# Microcontroller_and_Memory.net
KiCad netlist of a schematic drawn in Altium Designer
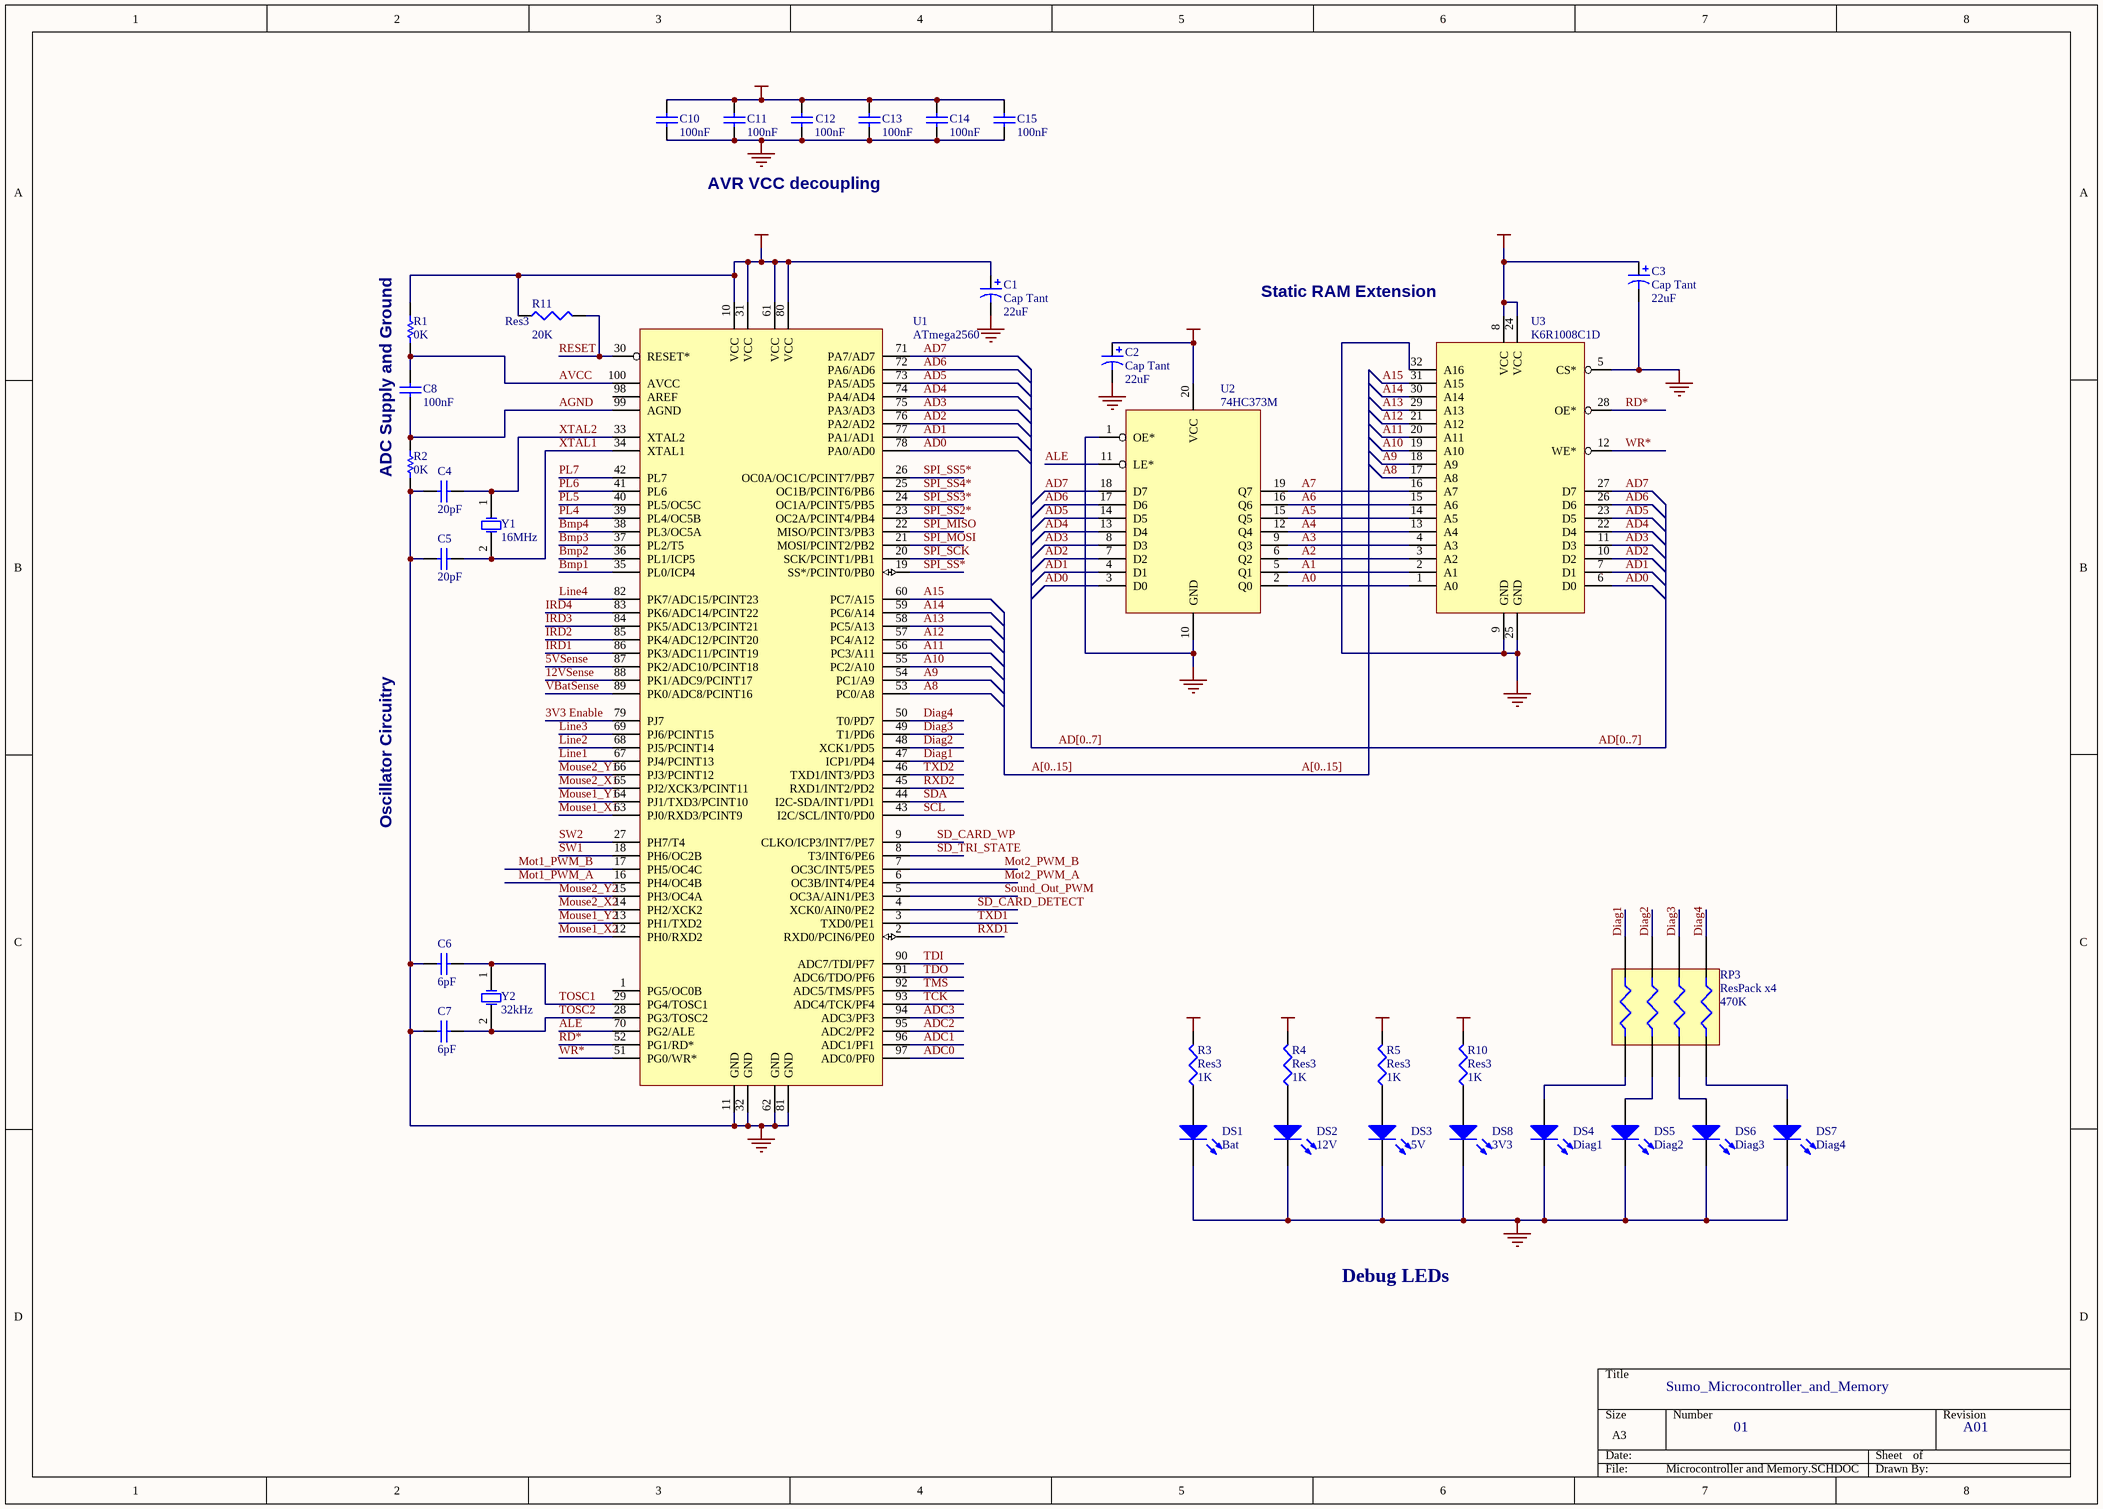
[diagram p0: Microcontroller and Memory.SCHDOC]

(export (version "E")
  (design (tool "Eeschema 10.0.6"))
  (components
    (comp (ref "C1")
      (value "Cap Tant")
      (footprint "CAPR5-4X5")
      (description "Polarized Capacitor (Axial)")
      (fields (field (name "ALTIUM_VALUE") "22uF") (field (name "PUBLISHER") "Altium Limited"))
      (libsource (lib "Miscellaneous Devices") (part "Cap Pol2"))
    )
    (comp (ref "C2")
      (value "Cap Tant")
      (footprint "CAPR5-4X5")
      (description "Polarized Capacitor (Axial)")
      (fields (field (name "ALTIUM_VALUE") "22uF") (field (name "PUBLISHER") "Altium Limited"))
      (libsource (lib "Miscellaneous Devices") (part "Cap Pol2"))
    )
    (comp (ref "C3")
      (value "Cap Tant")
      (footprint "CAPR5-4X5")
      (description "Polarized Capacitor (Axial)")
      (fields (field (name "ALTIUM_VALUE") "22uF") (field (name "PUBLISHER") "Altium Limited"))
      (libsource (lib "Miscellaneous Devices") (part "Cap Pol2"))
    )
    (comp (ref "C4")
      (value "20pF")
      (footprint "CC2012-0805")
      (description "Capacitor")
      (fields (field (name "PUBLISHER") "Altium Limited"))
      (libsource (lib "Miscellaneous Devices") (part "Cap"))
    )
    (comp (ref "C5")
      (value "20pF")
      (footprint "CC2012-0805")
      (description "Capacitor")
      (fields (field (name "PUBLISHER") "Altium Limited"))
      (libsource (lib "Miscellaneous Devices") (part "Cap"))
    )
    (comp (ref "C6")
      (value "6pF")
      (footprint "CC2012-0805")
      (description "Capacitor")
      (fields (field (name "PUBLISHER") "Altium Limited"))
      (libsource (lib "Miscellaneous Devices") (part "Cap"))
    )
    (comp (ref "C7")
      (value "6pF")
      (footprint "CC2012-0805")
      (description "Capacitor")
      (fields (field (name "PUBLISHER") "Altium Limited"))
      (libsource (lib "Miscellaneous Devices") (part "Cap"))
    )
    (comp (ref "C8")
      (value "100nF")
      (footprint "CC2012-0805")
      (description "Capacitor")
      (fields (field (name "PUBLISHER") "Altium Limited"))
      (libsource (lib "Miscellaneous Devices") (part "Cap"))
    )
    (comp (ref "C10")
      (value "100nF")
      (footprint "CC2012-0805")
      (description "Capacitor (Semiconductor SIM Model)")
      (fields (field (name "Comment") "Cap Semi") (field (name "PUBLISHER") "Altium Limited"))
      (libsource (lib "Miscellaneous Devices") (part "Cap Semi"))
    )
    (comp (ref "C11")
      (value "100nF")
      (footprint "CC2012-0805")
      (description "Capacitor (Semiconductor SIM Model)")
      (fields (field (name "Comment") "Cap Semi") (field (name "PUBLISHER") "Altium Limited"))
      (libsource (lib "Miscellaneous Devices") (part "Cap Semi"))
    )
    (comp (ref "C12")
      (value "100nF")
      (footprint "CC2012-0805")
      (description "Capacitor (Semiconductor SIM Model)")
      (fields (field (name "Comment") "Cap Semi") (field (name "PUBLISHER") "Altium Limited"))
      (libsource (lib "Miscellaneous Devices") (part "Cap Semi"))
    )
    (comp (ref "C13")
      (value "100nF")
      (footprint "CC2012-0805")
      (description "Capacitor (Semiconductor SIM Model)")
      (fields (field (name "Comment") "Cap Semi") (field (name "PUBLISHER") "Altium Limited"))
      (libsource (lib "Miscellaneous Devices") (part "Cap Semi"))
    )
    (comp (ref "C14")
      (value "100nF")
      (footprint "CC2012-0805")
      (description "Capacitor (Semiconductor SIM Model)")
      (fields (field (name "Comment") "Cap Semi") (field (name "PUBLISHER") "Altium Limited"))
      (libsource (lib "Miscellaneous Devices") (part "Cap Semi"))
    )
    (comp (ref "C15")
      (value "100nF")
      (footprint "CC2012-0805")
      (description "Capacitor (Semiconductor SIM Model)")
      (fields (field (name "Comment") "Cap Semi") (field (name "PUBLISHER") "Altium Limited"))
      (libsource (lib "Miscellaneous Devices") (part "Cap Semi"))
    )
    (comp (ref "DS1")
      (value "Bat")
      (footprint "SMD _LED")
      (description "Typical BLUE SiC LED")
      (fields (field (name "PUBLISHER") "Altium Limited"))
      (libsource (lib "Miscellaneous Devices") (part "LED3"))
    )
    (comp (ref "DS2")
      (value "12V")
      (footprint "SMD _LED")
      (description "Typical BLUE SiC LED")
      (fields (field (name "PUBLISHER") "Altium Limited"))
      (libsource (lib "Miscellaneous Devices") (part "LED3"))
    )
    (comp (ref "DS3")
      (value "5V")
      (footprint "SMD _LED")
      (description "Typical BLUE SiC LED")
      (fields (field (name "PUBLISHER") "Altium Limited"))
      (libsource (lib "Miscellaneous Devices") (part "LED3"))
    )
    (comp (ref "DS4")
      (value "Diag1")
      (footprint "SMD _LED")
      (description "Typical BLUE SiC LED")
      (fields (field (name "PUBLISHER") "Altium Limited"))
      (libsource (lib "Miscellaneous Devices") (part "LED3"))
    )
    (comp (ref "DS5")
      (value "Diag2")
      (footprint "SMD _LED")
      (description "Typical BLUE SiC LED")
      (fields (field (name "PUBLISHER") "Altium Limited"))
      (libsource (lib "Miscellaneous Devices") (part "LED3"))
    )
    (comp (ref "DS6")
      (value "Diag3")
      (footprint "SMD _LED")
      (description "Typical BLUE SiC LED")
      (fields (field (name "PUBLISHER") "Altium Limited"))
      (libsource (lib "Miscellaneous Devices") (part "LED3"))
    )
    (comp (ref "DS7")
      (value "Diag4")
      (footprint "SMD _LED")
      (description "Typical BLUE SiC LED")
      (fields (field (name "PUBLISHER") "Altium Limited"))
      (libsource (lib "Miscellaneous Devices") (part "LED3"))
    )
    (comp (ref "DS8")
      (value "3V3")
      (footprint "SMD _LED")
      (description "Typical BLUE SiC LED")
      (fields (field (name "PUBLISHER") "Altium Limited"))
      (libsource (lib "Miscellaneous Devices") (part "LED3"))
    )
    (comp (ref "R1")
      (value "0K")
      (footprint "AXIAL-0.3")
      (description "Resistor")
      (fields (field (name "PUBLISHER") "Altium Limited"))
      (libsource (lib "Miscellaneous Devices") (part "Res1"))
    )
    (comp (ref "R2")
      (value "0K")
      (footprint "AXIAL-0.3")
      (description "Resistor")
      (fields (field (name "PUBLISHER") "Altium Limited"))
      (libsource (lib "Miscellaneous Devices") (part "Res1"))
    )
    (comp (ref "R3")
      (value "Res3")
      (footprint "R2012-0805")
      (description "Resistor")
      (fields (field (name "ALTIUM_VALUE") "1K") (field (name "PUBLISHER") "Altium Limited"))
      (libsource (lib "Miscellaneous Devices") (part "Res3"))
    )
    (comp (ref "R4")
      (value "Res3")
      (footprint "R2012-0805")
      (description "Resistor")
      (fields (field (name "ALTIUM_VALUE") "1K") (field (name "PUBLISHER") "Altium Limited"))
      (libsource (lib "Miscellaneous Devices") (part "Res3"))
    )
    (comp (ref "R5")
      (value "Res3")
      (footprint "R2012-0805")
      (description "Resistor")
      (fields (field (name "ALTIUM_VALUE") "1K") (field (name "PUBLISHER") "Altium Limited"))
      (libsource (lib "Miscellaneous Devices") (part "Res3"))
    )
    (comp (ref "R10")
      (value "Res3")
      (footprint "R2012-0805")
      (description "Resistor")
      (fields (field (name "ALTIUM_VALUE") "1K") (field (name "PUBLISHER") "Altium Limited"))
      (libsource (lib "Miscellaneous Devices") (part "Res3"))
    )
    (comp (ref "R11")
      (value "Res3")
      (footprint "R2012-0805")
      (description "Resistor")
      (fields (field (name "ALTIUM_VALUE") "20K") (field (name "PUBLISHER") "Altium Limited"))
      (libsource (lib "Miscellaneous Devices") (part "Res3"))
    )
    (comp (ref "RP3")
      (value "ResPack x4")
      (footprint "4x0603 Resistor pack")
      (fields (field (name "ALTIUM_VALUE") "470K"))
      (libsource (lib "Sumo") (part "ResPack x4"))
    )
    (comp (ref "U1")
      (value "ATmega2560")
      (footprint "F-QFP14X14-G100/Z17N")
      (description "Atmel ATmega2560 MCU")
      (libsource (lib "Sumo") (part "ATmega2560"))
    )
    (comp (ref "U2")
      (value "74HC373M")
      (footprint "SO-G20/Y1.45")
      (description "Octal 8-bit D-type Latch")
      (libsource (lib "Schematic Library") (part "74373"))
    )
    (comp (ref "U3")
      (value "K6R1008C1D")
      (footprint "SO-G32/Y1.45")
      (description "Samsung 128Kx8 High-Speed Static RAM")
      (libsource (lib "Schematic Library") (part "K6R1008C1D"))
    )
    (comp (ref "Y1")
      (value "16MHz")
      (footprint "Crystal HC49SLF")
      (description "Crystal Oscillator")
      (fields (field (name "PUBLISHER") "Altium Limited"))
      (libsource (lib "Miscellaneous Devices") (part "XTAL"))
    )
    (comp (ref "Y2")
      (value "32kHz")
      (footprint "Crystal CFS206")
      (description "Crystal Oscillator")
      (fields (field (name "PUBLISHER") "Altium Limited"))
      (libsource (lib "Miscellaneous Devices") (part "XTAL"))
    )
  )
  (nets
    (net (code "1") (name "/3V3 Enable") (class "Default")
      (node (ref "U1") (pin "79") (pinfunction "PJ7_79") (pintype "passive"))
    )
    (net (code "2") (name "/5VSense") (class "Default")
      (node (ref "U1") (pin "87") (pinfunction "PK2/ADC10/PCINT18_87") (pintype "passive"))
    )
    (net (code "3") (name "/12VSense") (class "Default")
      (node (ref "U1") (pin "88") (pinfunction "PK1/ADC9/PCINT17_88") (pintype "passive"))
    )
    (net (code "4") (name "/A0") (class "Default")
      (node (ref "U2") (pin "2") (pinfunction "Q0_2") (pintype "passive"))
      (node (ref "U3") (pin "1") (pinfunction "A0_1") (pintype "passive"))
    )
    (net (code "5") (name "/A1") (class "Default")
      (node (ref "U2") (pin "5") (pinfunction "Q1_5") (pintype "passive"))
      (node (ref "U3") (pin "2") (pinfunction "A1_2") (pintype "passive"))
    )
    (net (code "6") (name "/A2") (class "Default")
      (node (ref "U2") (pin "6") (pinfunction "Q2_6") (pintype "passive"))
      (node (ref "U3") (pin "3") (pinfunction "A2_3") (pintype "passive"))
    )
    (net (code "7") (name "/A3") (class "Default")
      (node (ref "U2") (pin "9") (pinfunction "Q3_9") (pintype "passive"))
      (node (ref "U3") (pin "4") (pinfunction "A3_4") (pintype "passive"))
    )
    (net (code "8") (name "/A4") (class "Default")
      (node (ref "U2") (pin "12") (pinfunction "Q4_12") (pintype "passive"))
      (node (ref "U3") (pin "13") (pinfunction "A4_13") (pintype "passive"))
    )
    (net (code "9") (name "/A5") (class "Default")
      (node (ref "U2") (pin "15") (pinfunction "Q5_15") (pintype "passive"))
      (node (ref "U3") (pin "14") (pinfunction "A5_14") (pintype "passive"))
    )
    (net (code "10") (name "/A6") (class "Default")
      (node (ref "U2") (pin "16") (pinfunction "Q6_16") (pintype "passive"))
      (node (ref "U3") (pin "15") (pinfunction "A6_15") (pintype "passive"))
    )
    (net (code "11") (name "/A7") (class "Default")
      (node (ref "U2") (pin "19") (pinfunction "Q7_19") (pintype "passive"))
      (node (ref "U3") (pin "16") (pinfunction "A7_16") (pintype "passive"))
    )
    (net (code "12") (name "/A8") (class "Default")
      (node (ref "U1") (pin "53") (pinfunction "PC0/A8_53") (pintype "passive"))
      (node (ref "U3") (pin "17") (pinfunction "A8_17") (pintype "passive"))
    )
    (net (code "13") (name "/A9") (class "Default")
      (node (ref "U1") (pin "54") (pinfunction "PC1/A9_54") (pintype "passive"))
      (node (ref "U3") (pin "18") (pinfunction "A9_18") (pintype "passive"))
    )
    (net (code "14") (name "/A10") (class "Default")
      (node (ref "U1") (pin "55") (pinfunction "PC2/A10_55") (pintype "passive"))
      (node (ref "U3") (pin "19") (pinfunction "A10_19") (pintype "passive"))
    )
    (net (code "15") (name "/A11") (class "Default")
      (node (ref "U1") (pin "56") (pinfunction "PC3/A11_56") (pintype "passive"))
      (node (ref "U3") (pin "20") (pinfunction "A11_20") (pintype "passive"))
    )
    (net (code "16") (name "/A12") (class "Default")
      (node (ref "U1") (pin "57") (pinfunction "PC4/A12_57") (pintype "passive"))
      (node (ref "U3") (pin "21") (pinfunction "A12_21") (pintype "passive"))
    )
    (net (code "17") (name "/A13") (class "Default")
      (node (ref "U1") (pin "58") (pinfunction "PC5/A13_58") (pintype "passive"))
      (node (ref "U3") (pin "29") (pinfunction "A13_29") (pintype "passive"))
    )
    (net (code "18") (name "/A14") (class "Default")
      (node (ref "U1") (pin "59") (pinfunction "PC6/A14_59") (pintype "passive"))
      (node (ref "U3") (pin "30") (pinfunction "A14_30") (pintype "passive"))
    )
    (net (code "19") (name "/A15") (class "Default")
      (node (ref "U1") (pin "60") (pinfunction "PC7/A15_60") (pintype "passive"))
      (node (ref "U3") (pin "31") (pinfunction "A15_31") (pintype "passive"))
    )
    (net (code "20") (name "/AD0") (class "Default")
      (node (ref "U1") (pin "78") (pinfunction "PA0/AD0_78") (pintype "passive"))
      (node (ref "U2") (pin "3") (pinfunction "D0_3") (pintype "passive"))
      (node (ref "U3") (pin "6") (pinfunction "D0_6") (pintype "passive"))
    )
    (net (code "21") (name "/AD1") (class "Default")
      (node (ref "U1") (pin "77") (pinfunction "PA1/AD1_77") (pintype "passive"))
      (node (ref "U2") (pin "4") (pinfunction "D1_4") (pintype "passive"))
      (node (ref "U3") (pin "7") (pinfunction "D1_7") (pintype "passive"))
    )
    (net (code "22") (name "/AD2") (class "Default")
      (node (ref "U1") (pin "76") (pinfunction "PA2/AD2_76") (pintype "passive"))
      (node (ref "U2") (pin "7") (pinfunction "D2_7") (pintype "passive"))
      (node (ref "U3") (pin "10") (pinfunction "D2_10") (pintype "passive"))
    )
    (net (code "23") (name "/AD3") (class "Default")
      (node (ref "U1") (pin "75") (pinfunction "PA3/AD3_75") (pintype "passive"))
      (node (ref "U2") (pin "8") (pinfunction "D3_8") (pintype "passive"))
      (node (ref "U3") (pin "11") (pinfunction "D3_11") (pintype "passive"))
    )
    (net (code "24") (name "/AD4") (class "Default")
      (node (ref "U1") (pin "74") (pinfunction "PA4/AD4_74") (pintype "passive"))
      (node (ref "U2") (pin "13") (pinfunction "D4_13") (pintype "passive"))
      (node (ref "U3") (pin "22") (pinfunction "D4_22") (pintype "passive"))
    )
    (net (code "25") (name "/AD5") (class "Default")
      (node (ref "U1") (pin "73") (pinfunction "PA5/AD5_73") (pintype "passive"))
      (node (ref "U2") (pin "14") (pinfunction "D5_14") (pintype "passive"))
      (node (ref "U3") (pin "23") (pinfunction "D5_23") (pintype "passive"))
    )
    (net (code "26") (name "/AD6") (class "Default")
      (node (ref "U1") (pin "72") (pinfunction "PA6/AD6_72") (pintype "passive"))
      (node (ref "U2") (pin "17") (pinfunction "D6_17") (pintype "passive"))
      (node (ref "U3") (pin "26") (pinfunction "D6_26") (pintype "passive"))
    )
    (net (code "27") (name "/AD7") (class "Default")
      (node (ref "U1") (pin "71") (pinfunction "PA7/AD7_71") (pintype "passive"))
      (node (ref "U2") (pin "18") (pinfunction "D7_18") (pintype "passive"))
      (node (ref "U3") (pin "27") (pinfunction "D7_27") (pintype "passive"))
    )
    (net (code "28") (name "/ADC0") (class "Default")
      (node (ref "U1") (pin "97") (pinfunction "ADC0/PF0_97") (pintype "passive"))
    )
    (net (code "29") (name "/ADC1") (class "Default")
      (node (ref "U1") (pin "96") (pinfunction "ADC1/PF1_96") (pintype "passive"))
    )
    (net (code "30") (name "/ADC2") (class "Default")
      (node (ref "U1") (pin "95") (pinfunction "ADC2/PF2_95") (pintype "passive"))
    )
    (net (code "31") (name "/ADC3") (class "Default")
      (node (ref "U1") (pin "94") (pinfunction "ADC3/PF3_94") (pintype "passive"))
    )
    (net (code "33") (name "/AGND") (class "Default")
      (node (ref "C8") (pin "2") (pinfunction "2_2") (pintype "passive"))
      (node (ref "R2") (pin "2") (pinfunction "2_2") (pintype "passive"))
      (node (ref "U1") (pin "99") (pinfunction "AGND_99") (pintype "passive"))
    )
    (net (code "34") (name "/ALE") (class "Default")
      (node (ref "U1") (pin "70") (pinfunction "PG2/ALE_70") (pintype "passive"))
      (node (ref "U2") (pin "11") (pinfunction "LE*_11") (pintype "passive"))
    )
    (net (code "35") (name "/AVCC") (class "Default")
      (node (ref "C8") (pin "1") (pinfunction "1_1") (pintype "passive"))
      (node (ref "R1") (pin "1") (pinfunction "1_1") (pintype "passive"))
      (node (ref "U1") (pin "100") (pinfunction "AVCC_100") (pintype "passive"))
    )
    (net (code "37") (name "/Bmp1") (class "Default")
      (node (ref "U1") (pin "35") (pinfunction "PL0/ICP4_35") (pintype "passive"))
    )
    (net (code "38") (name "/Bmp2") (class "Default")
      (node (ref "U1") (pin "36") (pinfunction "PL1/ICP5_36") (pintype "passive"))
    )
    (net (code "39") (name "/Bmp3") (class "Default")
      (node (ref "U1") (pin "37") (pinfunction "PL2/T5_37") (pintype "passive"))
    )
    (net (code "40") (name "/Bmp4") (class "Default")
      (node (ref "U1") (pin "38") (pinfunction "PL3/OC5A_38") (pintype "passive"))
    )
    (net (code "41") (name "/Diag1") (class "Default")
      (node (ref "RP3") (pin "8") (pintype "passive"))
      (node (ref "U1") (pin "47") (pinfunction "ICP1/PD4_47") (pintype "passive"))
    )
    (net (code "42") (name "/Diag2") (class "Default")
      (node (ref "RP3") (pin "7") (pintype "passive"))
      (node (ref "U1") (pin "48") (pinfunction "XCK1/PD5_48") (pintype "passive"))
    )
    (net (code "43") (name "/Diag3") (class "Default")
      (node (ref "RP3") (pin "6") (pintype "passive"))
      (node (ref "U1") (pin "49") (pinfunction "T1/PD6_49") (pintype "passive"))
    )
    (net (code "44") (name "/Diag4") (class "Default")
      (node (ref "RP3") (pin "5") (pintype "passive"))
      (node (ref "U1") (pin "50") (pinfunction "T0/PD7_50") (pintype "passive"))
    )
    (net (code "45") (name "/IRD1") (class "Default")
      (node (ref "U1") (pin "86") (pinfunction "PK3/ADC11/PCINT19_86") (pintype "passive"))
    )
    (net (code "46") (name "/IRD2") (class "Default")
      (node (ref "U1") (pin "85") (pinfunction "PK4/ADC12/PCINT20_85") (pintype "passive"))
    )
    (net (code "47") (name "/IRD3") (class "Default")
      (node (ref "U1") (pin "84") (pinfunction "PK5/ADC13/PCINT21_84") (pintype "passive"))
    )
    (net (code "48") (name "/IRD4") (class "Default")
      (node (ref "U1") (pin "83") (pinfunction "PK6/ADC14/PCINT22_83") (pintype "passive"))
    )
    (net (code "49") (name "/Line1") (class "Default")
      (node (ref "U1") (pin "67") (pinfunction "PJ4/PCINT13_67") (pintype "passive"))
    )
    (net (code "50") (name "/Line2") (class "Default")
      (node (ref "U1") (pin "68") (pinfunction "PJ5/PCINT14_68") (pintype "passive"))
    )
    (net (code "51") (name "/Line3") (class "Default")
      (node (ref "U1") (pin "69") (pinfunction "PJ6/PCINT15_69") (pintype "passive"))
    )
    (net (code "52") (name "/Line4") (class "Default")
      (node (ref "U1") (pin "82") (pinfunction "PK7/ADC15/PCINT23_82") (pintype "passive"))
    )
    (net (code "53") (name "/Mot1_PWM_A") (class "Default")
      (node (ref "U1") (pin "16") (pinfunction "PH4/OC4B_16") (pintype "passive"))
    )
    (net (code "54") (name "/Mot1_PWM_B") (class "Default")
      (node (ref "U1") (pin "17") (pinfunction "PH5/OC4C_17") (pintype "passive"))
    )
    (net (code "55") (name "/Mot2_PWM_A") (class "Default")
      (node (ref "U1") (pin "6") (pinfunction "OC3B/INT4/PE4_6") (pintype "passive"))
    )
    (net (code "56") (name "/Mot2_PWM_B") (class "Default")
      (node (ref "U1") (pin "7") (pinfunction "OC3C/INT5/PE5_7") (pintype "passive"))
    )
    (net (code "57") (name "/Mouse1_X1") (class "Default")
      (node (ref "U1") (pin "63") (pinfunction "PJ0/RXD3/PCINT9_63") (pintype "passive"))
    )
    (net (code "58") (name "/Mouse1_X2") (class "Default")
      (node (ref "U1") (pin "12") (pinfunction "PH0/RXD2_12") (pintype "passive"))
    )
    (net (code "59") (name "/Mouse1_Y1") (class "Default")
      (node (ref "U1") (pin "64") (pinfunction "PJ1/TXD3/PCINT10_64") (pintype "passive"))
    )
    (net (code "60") (name "/Mouse1_Y2") (class "Default")
      (node (ref "U1") (pin "13") (pinfunction "PH1/TXD2_13") (pintype "passive"))
    )
    (net (code "61") (name "/Mouse2_X1") (class "Default")
      (node (ref "U1") (pin "65") (pinfunction "PJ2/XCK3/PCINT11_65") (pintype "passive"))
    )
    (net (code "62") (name "/Mouse2_X2") (class "Default")
      (node (ref "U1") (pin "14") (pinfunction "PH2/XCK2_14") (pintype "passive"))
    )
    (net (code "63") (name "/Mouse2_Y1") (class "Default")
      (node (ref "U1") (pin "66") (pinfunction "PJ3/PCINT12_66") (pintype "passive"))
    )
    (net (code "64") (name "/Mouse2_Y2") (class "Default")
      (node (ref "U1") (pin "15") (pinfunction "PH3/OC4A_15") (pintype "passive"))
    )
    (net (code "65") (name "/PL4") (class "Default")
      (node (ref "U1") (pin "39") (pinfunction "PL4/OC5B_39") (pintype "passive"))
    )
    (net (code "66") (name "/PL5") (class "Default")
      (node (ref "U1") (pin "40") (pinfunction "PL5/OC5C_40") (pintype "passive"))
    )
    (net (code "67") (name "/PL6") (class "Default")
      (node (ref "U1") (pin "41") (pinfunction "PL6_41") (pintype "passive"))
    )
    (net (code "68") (name "/PL7") (class "Default")
      (node (ref "U1") (pin "42") (pinfunction "PL7_42") (pintype "passive"))
    )
    (net (code "69") (name "/RD*") (class "Default")
      (node (ref "U1") (pin "52") (pinfunction "PG1/RD*_52") (pintype "passive"))
      (node (ref "U3") (pin "28") (pinfunction "OE*_28") (pintype "passive"))
    )
    (net (code "70") (name "/RESET") (class "Default")
      (node (ref "R11") (pin "2") (pinfunction "2_2") (pintype "passive"))
      (node (ref "U1") (pin "30") (pinfunction "RESET*_30") (pintype "passive"))
    )
    (net (code "71") (name "/RXD1") (class "Default")
      (node (ref "U1") (pin "2") (pinfunction "RXD0/PCIN6/PE0_2") (pintype "bidirectional"))
    )
    (net (code "72") (name "/RXD2") (class "Default")
      (node (ref "U1") (pin "45") (pinfunction "RXD1/INT2/PD2_45") (pintype "passive"))
    )
    (net (code "73") (name "/SCL") (class "Default")
      (node (ref "U1") (pin "43") (pinfunction "I2C/SCL/INT0/PD0_43") (pintype "passive"))
    )
    (net (code "74") (name "/SDA") (class "Default")
      (node (ref "U1") (pin "44") (pinfunction "I2C-SDA/INT1/PD1_44") (pintype "passive"))
    )
    (net (code "75") (name "/SD_CARD_DETECT") (class "Default")
      (node (ref "U1") (pin "4") (pinfunction "XCK0/AIN0/PE2_4") (pintype "passive"))
    )
    (net (code "76") (name "/SD_CARD_WP") (class "Default")
      (node (ref "U1") (pin "9") (pinfunction "CLKO/ICP3/INT7/PE7_9") (pintype "passive"))
    )
    (net (code "77") (name "/SD_TRI_STATE") (class "Default")
      (node (ref "U1") (pin "8") (pinfunction "T3/INT6/PE6_8") (pintype "passive"))
    )
    (net (code "78") (name "/SPI_MISO") (class "Default")
      (node (ref "U1") (pin "22") (pinfunction "MISO/PCINT3/PB3_22") (pintype "passive"))
    )
    (net (code "79") (name "/SPI_MOSI") (class "Default")
      (node (ref "U1") (pin "21") (pinfunction "MOSI/PCINT2/PB2_21") (pintype "passive"))
    )
    (net (code "80") (name "/SPI_SCK") (class "Default")
      (node (ref "U1") (pin "20") (pinfunction "SCK/PCINT1/PB1_20") (pintype "passive"))
    )
    (net (code "81") (name "/SPI_SS*") (class "Default")
      (node (ref "U1") (pin "19") (pinfunction "SS*/PCINT0/PB0_19") (pintype "bidirectional"))
    )
    (net (code "82") (name "/SPI_SS2*") (class "Default")
      (node (ref "U1") (pin "23") (pinfunction "OC2A/PCINT4/PB4_23") (pintype "passive"))
    )
    (net (code "83") (name "/SPI_SS3*") (class "Default")
      (node (ref "U1") (pin "24") (pinfunction "OC1A/PCINT5/PB5_24") (pintype "passive"))
    )
    (net (code "84") (name "/SPI_SS4*") (class "Default")
      (node (ref "U1") (pin "25") (pinfunction "OC1B/PCINT6/PB6_25") (pintype "passive"))
    )
    (net (code "85") (name "/SPI_SS5*") (class "Default")
      (node (ref "U1") (pin "26") (pinfunction "OC0A/OC1C/PCINT7/PB7_26") (pintype "passive"))
    )
    (net (code "86") (name "/SW1") (class "Default")
      (node (ref "U1") (pin "18") (pinfunction "PH6/OC2B_18") (pintype "passive"))
    )
    (net (code "87") (name "/SW2") (class "Default")
      (node (ref "U1") (pin "27") (pinfunction "PH7/T4_27") (pintype "passive"))
    )
    (net (code "88") (name "/Sound_Out_PWM") (class "Default")
      (node (ref "U1") (pin "5") (pinfunction "OC3A/AIN1/PE3_5") (pintype "passive"))
    )
    (net (code "89") (name "/TCK") (class "Default")
      (node (ref "U1") (pin "93") (pinfunction "ADC4/TCK/PF4_93") (pintype "passive"))
    )
    (net (code "90") (name "/TDI") (class "Default")
      (node (ref "U1") (pin "90") (pinfunction "ADC7/TDI/PF7_90") (pintype "passive"))
    )
    (net (code "91") (name "/TDO") (class "Default")
      (node (ref "U1") (pin "91") (pinfunction "ADC6/TDO/PF6_91") (pintype "passive"))
    )
    (net (code "92") (name "/TMS") (class "Default")
      (node (ref "U1") (pin "92") (pinfunction "ADC5/TMS/PF5_92") (pintype "passive"))
    )
    (net (code "93") (name "/TOSC1") (class "Default")
      (node (ref "C6") (pin "2") (pinfunction "2_2") (pintype "passive"))
      (node (ref "U1") (pin "29") (pinfunction "PG4/TOSC1_29") (pintype "passive"))
      (node (ref "Y2") (pin "1") (pinfunction "OSC1_1") (pintype "passive"))
    )
    (net (code "94") (name "/TOSC2") (class "Default")
      (node (ref "C7") (pin "2") (pinfunction "2_2") (pintype "passive"))
      (node (ref "U1") (pin "28") (pinfunction "PG3/TOSC2_28") (pintype "passive"))
      (node (ref "Y2") (pin "2") (pinfunction "OSC2_2") (pintype "passive"))
    )
    (net (code "95") (name "/TXD1") (class "Default")
      (node (ref "U1") (pin "3") (pinfunction "TXD0/PE1_3") (pintype "passive"))
    )
    (net (code "96") (name "/TXD2") (class "Default")
      (node (ref "U1") (pin "46") (pinfunction "TXD1/INT3/PD3_46") (pintype "passive"))
    )
    (net (code "97") (name "/VBatSense") (class "Default")
      (node (ref "U1") (pin "89") (pinfunction "PK0/ADC8/PCINT16_89") (pintype "passive"))
    )
    (net (code "98") (name "/WR*") (class "Default")
      (node (ref "U1") (pin "51") (pinfunction "PG0/WR*_51") (pintype "passive"))
      (node (ref "U3") (pin "12") (pinfunction "WE*_12") (pintype "passive"))
    )
    (net (code "99") (name "/XTAL1") (class "Default")
      (node (ref "C5") (pin "2") (pinfunction "2_2") (pintype "passive"))
      (node (ref "U1") (pin "34") (pinfunction "XTAL1_34") (pintype "passive"))
      (node (ref "Y1") (pin "2") (pinfunction "OSC2_2") (pintype "passive"))
    )
    (net (code "100") (name "/XTAL2") (class "Default")
      (node (ref "C4") (pin "2") (pinfunction "2_2") (pintype "passive"))
      (node (ref "U1") (pin "33") (pinfunction "XTAL2_33") (pintype "passive"))
      (node (ref "Y1") (pin "1") (pinfunction "OSC1_1") (pintype "passive"))
    )
    (net (code "101") (name "3V3") (class "Default")
      (node (ref "R10") (pin "2") (pinfunction "2_2") (pintype "passive"))
    )
    (net (code "102") (name "5V") (class "Default")
      (node (ref "C1") (pin "1") (pinfunction "1_1") (pintype "passive"))
      (node (ref "C10") (pin "2") (pinfunction "2_2") (pintype "passive"))
      (node (ref "C11") (pin "2") (pinfunction "2_2") (pintype "passive"))
      (node (ref "C12") (pin "2") (pinfunction "2_2") (pintype "passive"))
      (node (ref "C13") (pin "2") (pinfunction "2_2") (pintype "passive"))
      (node (ref "C14") (pin "2") (pinfunction "2_2") (pintype "passive"))
      (node (ref "C15") (pin "2") (pinfunction "2_2") (pintype "passive"))
      (node (ref "C2") (pin "1") (pinfunction "1_1") (pintype "passive"))
      (node (ref "C3") (pin "1") (pinfunction "1_1") (pintype "passive"))
      (node (ref "R1") (pin "2") (pinfunction "2_2") (pintype "passive"))
      (node (ref "R11") (pin "1") (pinfunction "1_1") (pintype "passive"))
      (node (ref "R5") (pin "2") (pinfunction "2_2") (pintype "passive"))
      (node (ref "U1") (pin "10") (pinfunction "VCC_10") (pintype "passive"))
      (node (ref "U1") (pin "31") (pinfunction "VCC_31") (pintype "passive"))
      (node (ref "U1") (pin "61") (pinfunction "VCC_61") (pintype "passive"))
      (node (ref "U1") (pin "80") (pinfunction "VCC_80") (pintype "passive"))
      (node (ref "U2") (pin "20") (pinfunction "VCC_20") (pintype "passive"))
      (node (ref "U3") (pin "24") (pinfunction "VCC_24") (pintype "passive"))
      (node (ref "U3") (pin "8") (pinfunction "VCC_8") (pintype "passive"))
    )
    (net (code "103") (name "12V") (class "Default")
      (node (ref "R4") (pin "2") (pinfunction "2_2") (pintype "passive"))
    )
    (net (code "104") (name "GND") (class "Default")
      (node (ref "C1") (pin "2") (pinfunction "2_2") (pintype "passive"))
      (node (ref "C10") (pin "1") (pinfunction "1_1") (pintype "passive"))
      (node (ref "C11") (pin "1") (pinfunction "1_1") (pintype "passive"))
      (node (ref "C12") (pin "1") (pinfunction "1_1") (pintype "passive"))
      (node (ref "C13") (pin "1") (pinfunction "1_1") (pintype "passive"))
      (node (ref "C14") (pin "1") (pinfunction "1_1") (pintype "passive"))
      (node (ref "C15") (pin "1") (pinfunction "1_1") (pintype "passive"))
      (node (ref "C2") (pin "2") (pinfunction "2_2") (pintype "passive"))
      (node (ref "C3") (pin "2") (pinfunction "2_2") (pintype "passive"))
      (node (ref "C4") (pin "1") (pinfunction "1_1") (pintype "passive"))
      (node (ref "C5") (pin "1") (pinfunction "1_1") (pintype "passive"))
      (node (ref "C6") (pin "1") (pinfunction "1_1") (pintype "passive"))
      (node (ref "C7") (pin "1") (pinfunction "1_1") (pintype "passive"))
      (node (ref "DS1") (pin "2") (pinfunction "K_2") (pintype "passive"))
      (node (ref "DS2") (pin "2") (pinfunction "K_2") (pintype "passive"))
      (node (ref "DS3") (pin "2") (pinfunction "K_2") (pintype "passive"))
      (node (ref "DS4") (pin "2") (pinfunction "K_2") (pintype "passive"))
      (node (ref "DS5") (pin "2") (pinfunction "K_2") (pintype "passive"))
      (node (ref "DS6") (pin "2") (pinfunction "K_2") (pintype "passive"))
      (node (ref "DS7") (pin "2") (pinfunction "K_2") (pintype "passive"))
      (node (ref "DS8") (pin "2") (pinfunction "K_2") (pintype "passive"))
      (node (ref "R2") (pin "1") (pinfunction "1_1") (pintype "passive"))
      (node (ref "U1") (pin "11") (pinfunction "GND_11") (pintype "passive"))
      (node (ref "U1") (pin "32") (pinfunction "GND_32") (pintype "passive"))
      (node (ref "U1") (pin "62") (pinfunction "GND_62") (pintype "passive"))
      (node (ref "U1") (pin "81") (pinfunction "GND_81") (pintype "passive"))
      (node (ref "U2") (pin "1") (pinfunction "OE*_1") (pintype "passive"))
      (node (ref "U2") (pin "10") (pinfunction "GND_10") (pintype "passive"))
      (node (ref "U3") (pin "25") (pinfunction "GND_25") (pintype "passive"))
      (node (ref "U3") (pin "32") (pinfunction "A16_32") (pintype "passive"))
      (node (ref "U3") (pin "5") (pinfunction "CS*_5") (pintype "passive"))
      (node (ref "U3") (pin "9") (pinfunction "GND_9") (pintype "passive"))
    )
    (net (code "105") (name "Net-(DS1-A)") (class "Default")
      (node (ref "DS1") (pin "1") (pinfunction "A_1") (pintype "passive"))
      (node (ref "R3") (pin "1") (pinfunction "1_1") (pintype "passive"))
    )
    (net (code "106") (name "Net-(DS2-A)") (class "Default")
      (node (ref "DS2") (pin "1") (pinfunction "A_1") (pintype "passive"))
      (node (ref "R4") (pin "1") (pinfunction "1_1") (pintype "passive"))
    )
    (net (code "107") (name "Net-(DS3-A)") (class "Default")
      (node (ref "DS3") (pin "1") (pinfunction "A_1") (pintype "passive"))
      (node (ref "R5") (pin "1") (pinfunction "1_1") (pintype "passive"))
    )
    (net (code "108") (name "Net-(DS4-A)") (class "Default")
      (node (ref "DS4") (pin "1") (pinfunction "A_1") (pintype "passive"))
      (node (ref "RP3") (pin "1") (pintype "passive"))
    )
    (net (code "109") (name "Net-(DS5-A)") (class "Default")
      (node (ref "DS5") (pin "1") (pinfunction "A_1") (pintype "passive"))
      (node (ref "RP3") (pin "2") (pintype "passive"))
    )
    (net (code "110") (name "Net-(DS6-A)") (class "Default")
      (node (ref "DS6") (pin "1") (pinfunction "A_1") (pintype "passive"))
      (node (ref "RP3") (pin "3") (pintype "passive"))
    )
    (net (code "111") (name "Net-(DS7-A)") (class "Default")
      (node (ref "DS7") (pin "1") (pinfunction "A_1") (pintype "passive"))
      (node (ref "RP3") (pin "4") (pintype "passive"))
    )
    (net (code "112") (name "Net-(DS8-A)") (class "Default")
      (node (ref "DS8") (pin "1") (pinfunction "A_1") (pintype "passive"))
      (node (ref "R10") (pin "1") (pinfunction "1_1") (pintype "passive"))
    )
    (net (code "113") (name "VBat") (class "Default")
      (node (ref "R3") (pin "2") (pinfunction "2_2") (pintype "passive"))
    )
    (net (code "114") (name "unconnected-(U1-AREF-Pad98)") (class "Default")
      (node (ref "U1") (pin "98") (pinfunction "AREF_98") (pintype "passive"))
    )
    (net (code "115") (name "unconnected-(U1-PG5{slash}OC0B-Pad1)") (class "Default")
      (node (ref "U1") (pin "1") (pinfunction "PG5/OC0B_1") (pintype "passive"))
    )
  )
)
